# LED_Ribbon.net
KiCad netlist of a schematic drawn in Altium Designer
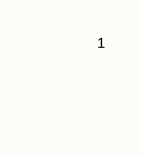
[diagram p0: LED Ribbon.SchDoc, top right]
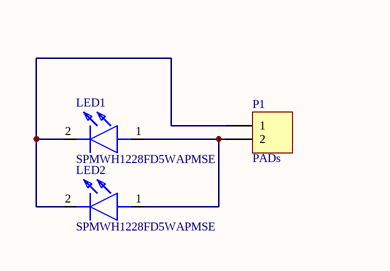
[diagram p1: LED Ribbon.SchDoc, bottom left]

(export (version "E")
  (design (tool "Eeschema 10.0.6"))
  (components
    (comp (ref "LED1")
      (value "SPMWH1228FD5WAPMSE")
      (footprint "SamacSys:SPMWH1228FD5WAPMSE")
      (description "LED")
      (libsource (lib "*") (part "SPMWH1228FD5WAPMSE"))
    )
    (comp (ref "LED2")
      (value "SPMWH1228FD5WAPMSE")
      (footprint "SamacSys:SPMWH1228FD5WAPMSE")
      (description "LED")
      (libsource (lib "*") (part "SPMWH1228FD5WAPMSE"))
    )
    (comp (ref "P1")
      (value "PADs")
      (footprint "HDR1X2")
      (description "Header, 2-Pin")
      (fields (field (name "PUBLISHER") "Altium Limited"))
      (libsource (lib "Miscellaneous Connectors") (part "Header 2"))
    )
  )
  (nets
    (net (code "1") (name "Net-(LED1-A)") (class "Default")
      (node (ref "LED1") (pin "1") (pinfunction "A_1") (pintype "passive"))
      (node (ref "LED2") (pin "1") (pinfunction "A_1") (pintype "passive"))
      (node (ref "P1") (pin "2") (pinfunction "2_2") (pintype "passive"))
    )
    (net (code "2") (name "Net-(LED1-K)") (class "Default")
      (node (ref "LED1") (pin "2") (pinfunction "K_2") (pintype "passive"))
      (node (ref "LED2") (pin "2") (pinfunction "K_2") (pintype "passive"))
      (node (ref "P1") (pin "1") (pinfunction "1_1") (pintype "passive"))
    )
  )
)
